# SCH_DFM_PCB_2023-04-27.net
KiCad netlist of a schematic drawn in EasyEDA
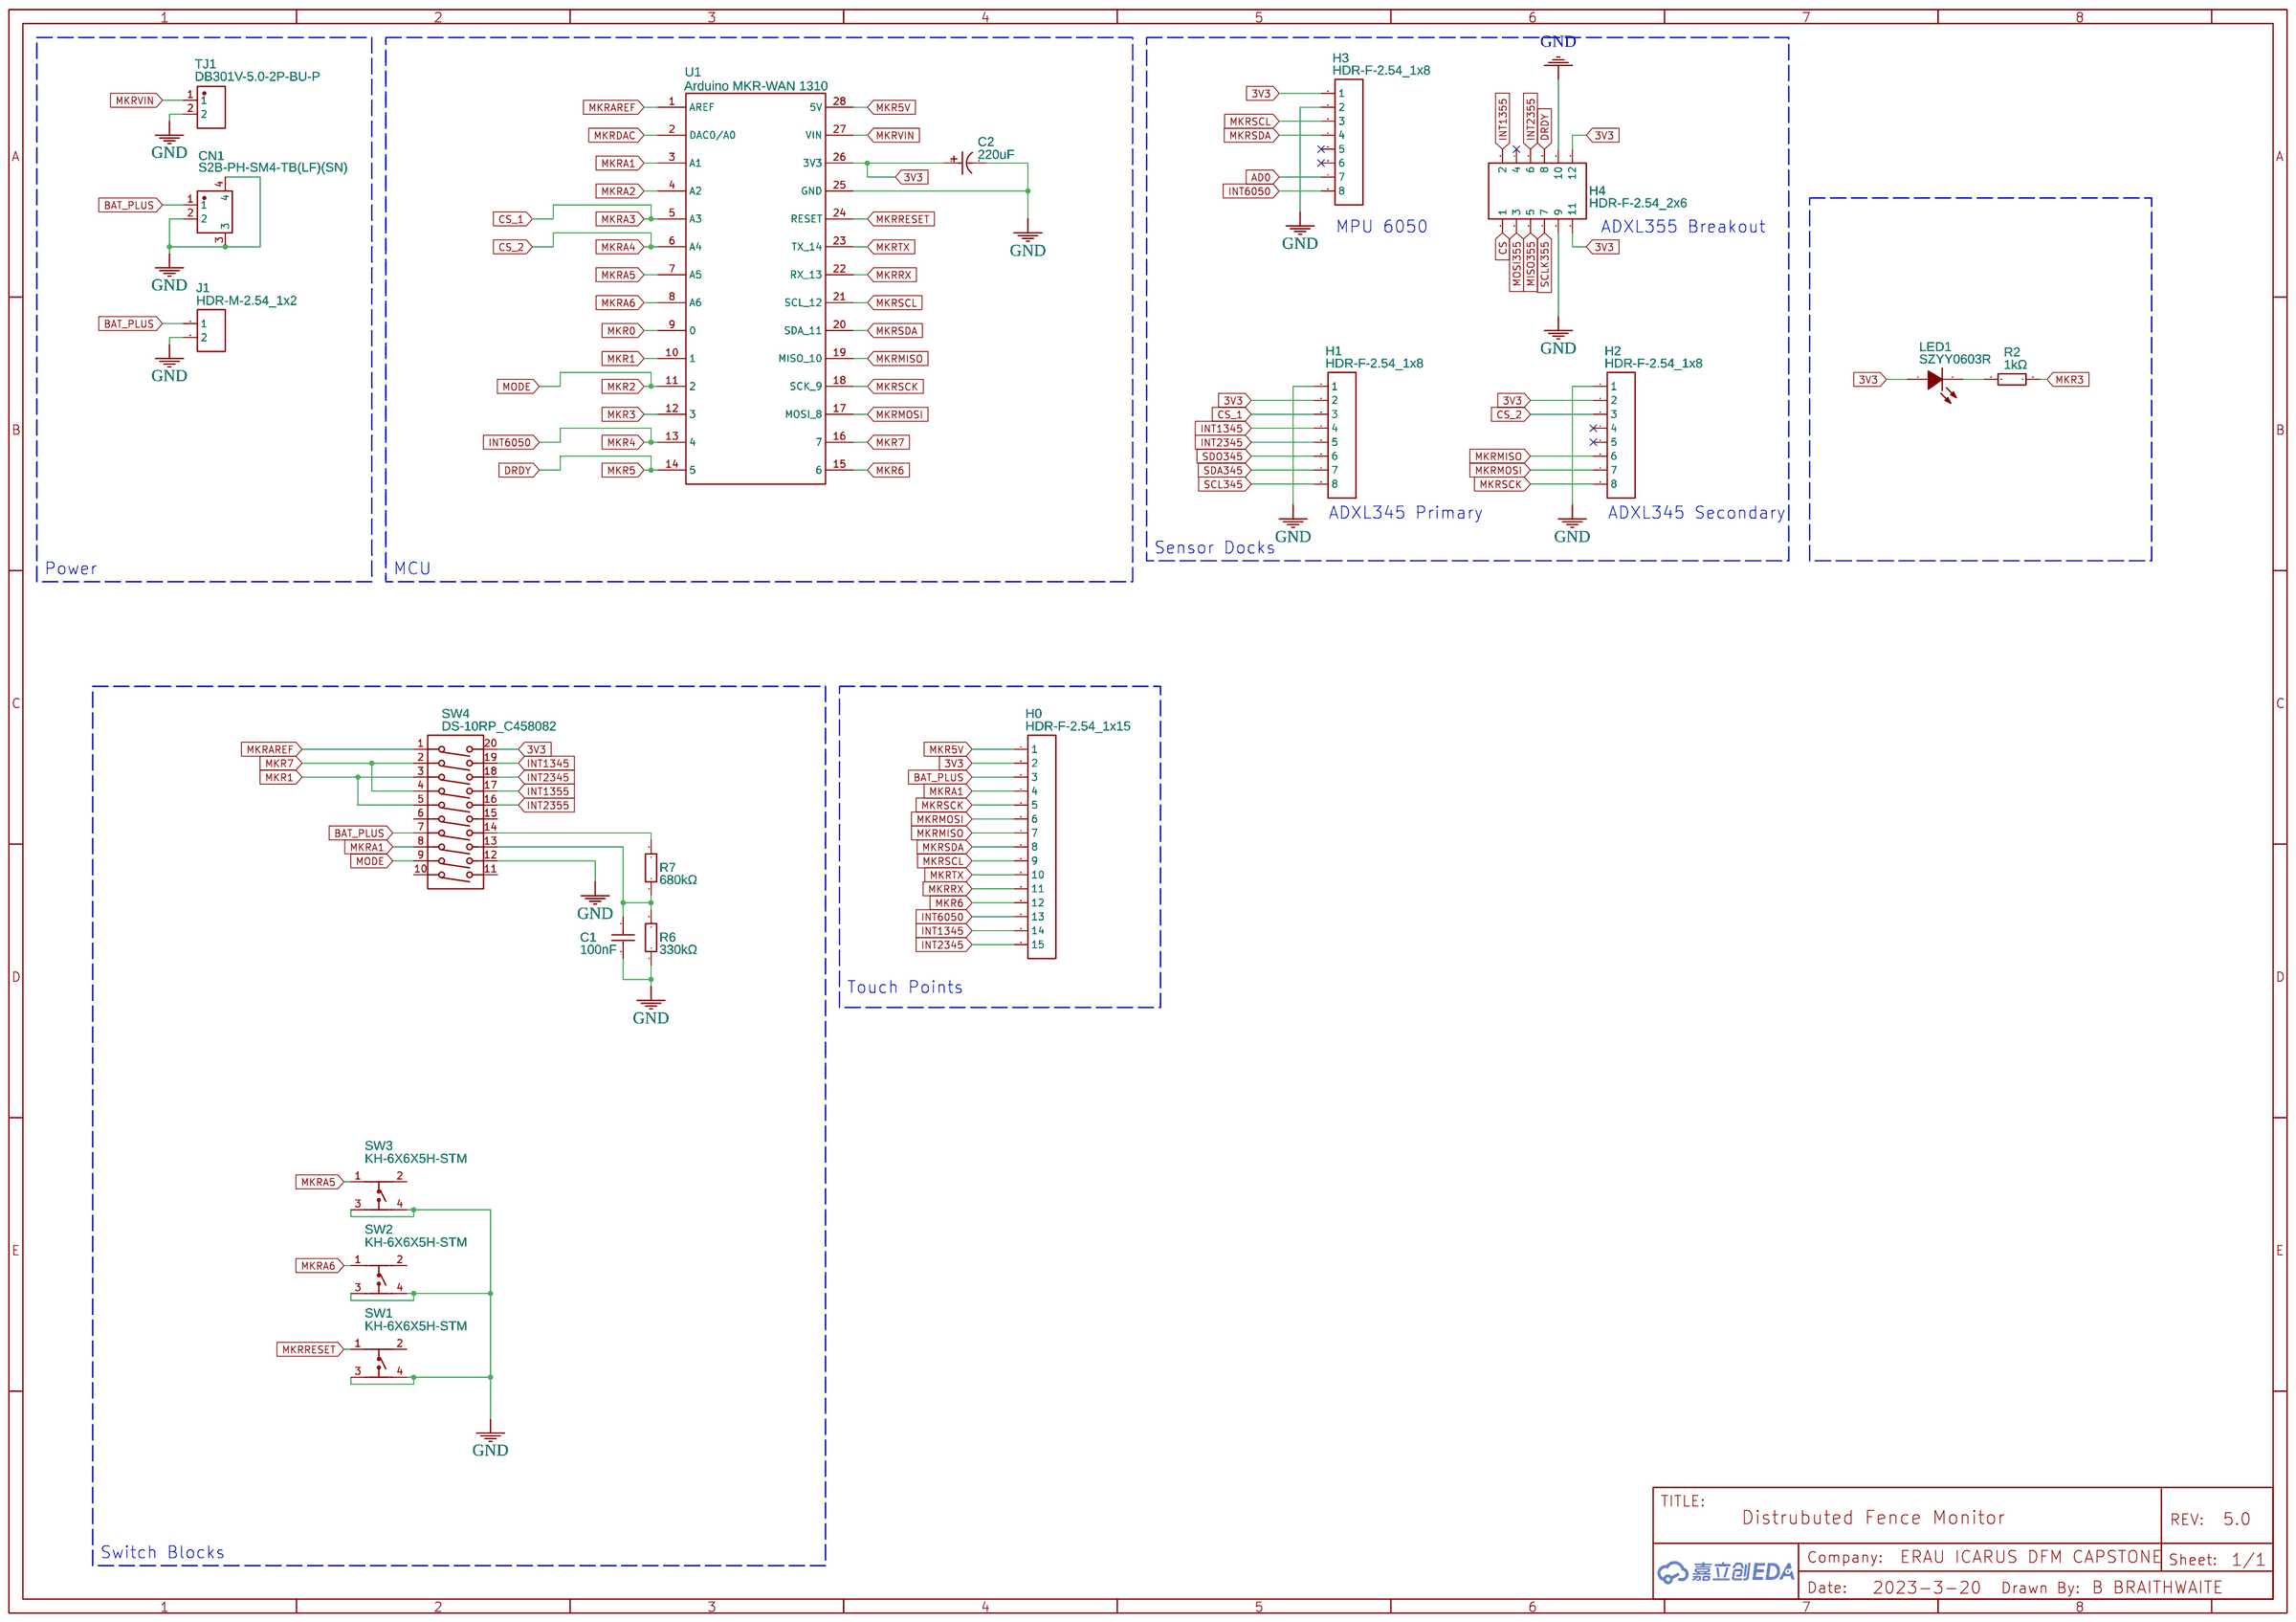
[diagram p0: schematic sheet]

(export (version "E")
  (design (tool "Eeschema 10.0.6"))
  (components
    (comp (ref "C1")
      (value "100nF")
      (fields
        (field (name "BOM_Manufacturer Part") "0603B104K500NT")
        (field (name "BOM_Supplier Part") "C30926")
      )
      (libsource (lib "") (part "0603B104K500NT"))
    )
    (comp (ref "C2")
      (value "220uF")
      (fields
        (field (name "BOM_Manufacturer Part") "RVT1A221M0605")
        (field (name "BOM_Supplier Part") "C72494")
      )
      (libsource (lib "") (part "RVT1A221M0605-C72494"))
    )
    (comp (ref "CN1")
      (value "S2B-PH-SM4-TB(LF)(SN)")
      (fields (field (name "BOM_Supplier Part") "C295747"))
      (libsource (lib "") (part "S2B-PH-SM4-TB(LF)(SN)"))
    )
    (comp (ref "H0")
      (value "HDR-F-2.54_1x15")
      (fields (field (name "BOM_Supplier Part") "C124408"))
      (libsource (lib "") (part "HDR-F-2.54_1x15"))
    )
    (comp (ref "H1")
      (value "HDR-F-2.54_1x8")
      (fields (field (name "BOM_Supplier Part") "C225505"))
      (libsource (lib "") (part "HDR-F-2.54_1x8"))
    )
    (comp (ref "H2")
      (value "HDR-F-2.54_1x8")
      (fields (field (name "BOM_Supplier Part") "C225505"))
      (libsource (lib "") (part "HDR-F-2.54_1x8"))
    )
    (comp (ref "H3")
      (value "HDR-F-2.54_1x8")
      (fields (field (name "BOM_Supplier Part") "C225505"))
      (libsource (lib "") (part "HDR-F-2.54_1x8"))
    )
    (comp (ref "H4")
      (value "HDR-F-2.54_2x6")
      (fields (field (name "BOM_Supplier Part") "C36191"))
      (libsource (lib "") (part "HDR-F-2.54_2x6"))
    )
    (comp (ref "J1")
      (value "HDR-M-2.54_1x2")
      (fields (field (name "BOM_Supplier Part") "C124375"))
      (libsource (lib "") (part "HDR-M-2.54_1x2"))
    )
    (comp (ref "LED1")
      (value "SZYY0603R")
      (fields (field (name "BOM_Supplier Part") "C434419"))
      (libsource (lib "") (part "SZYY0603R"))
    )
    (comp (ref "R2")
      (value "1kΩ")
      (fields
        (field (name "BOM_Manufacturer Part") "0805W8F1001T5E")
        (field (name "BOM_Supplier Part") "C17513")
      )
      (libsource (lib "") (part "0805W8F1001T5E"))
    )
    (comp (ref "R6")
      (value "330kΩ")
      (fields
        (field (name "BOM_Manufacturer Part") "0805W8F3303T5E")
        (field (name "BOM_Supplier Part") "C17629")
      )
      (libsource (lib "") (part "0805W8F3303T5E"))
    )
    (comp (ref "R7")
      (value "680kΩ")
      (fields
        (field (name "BOM_Manufacturer Part") "0805W8F6803T5E")
        (field (name "BOM_Supplier Part") "C17797")
      )
      (libsource (lib "") (part "0805W8F6803T5E"))
    )
    (comp (ref "SW1")
      (value "KH-6X6X5H-STM")
      (fields (field (name "BOM_Supplier Part") "C2837531"))
      (libsource (lib "") (part "KH-6X6X5H-STM"))
    )
    (comp (ref "SW2")
      (value "KH-6X6X5H-STM")
      (fields (field (name "BOM_Supplier Part") "C2837531"))
      (libsource (lib "") (part "KH-6X6X5H-STM"))
    )
    (comp (ref "SW3")
      (value "KH-6X6X5H-STM")
      (fields (field (name "BOM_Supplier Part") "C2837531"))
      (libsource (lib "") (part "KH-6X6X5H-STM"))
    )
    (comp (ref "SW4")
      (value "DS-10RP_C458082")
      (fields (field (name "BOM_Manufacturer Part") "DS-10RP") (field (name "BOM_Supplier Part") "C458082"))
      (libsource (lib "") (part "DS-10RP_C458082"))
    )
    (comp (ref "TJ1")
      (value "DB301V-5.0-2P-BU-P")
      (fields (field (name "BOM_Supplier Part") "C430621"))
      (libsource (lib "") (part "DB301V-5.0-2P-BU-P"))
    )
    (comp (ref "U1")
      (value "Arduino MKR-WAN 1310")
      (fields (field (name "BOM_Manufacturer Part") "Arduino MKR GSM 1400"))
      (libsource (lib "") (part "Arduino MKR-WAN 1310"))
    )
  )
  (nets
    (net (code "1") (name "3V3") (class "Default")
      (node (ref "C2") (pin "1") (pinfunction "1_1") (pintype "input"))
      (node (ref "H0") (pin "2") (pinfunction "2_2") (pintype "unspecified"))
      (node (ref "H1") (pin "2") (pinfunction "2_2") (pintype "unspecified"))
      (node (ref "H2") (pin "2") (pinfunction "2_2") (pintype "unspecified"))
      (node (ref "H3") (pin "1") (pinfunction "1_1") (pintype "unspecified"))
      (node (ref "H4") (pin "11") (pinfunction "11_11") (pintype "input"))
      (node (ref "H4") (pin "12") (pinfunction "12_12") (pintype "input"))
      (node (ref "LED1") (pin "1") (pinfunction "+_1") (pintype "unspecified"))
      (node (ref "SW4") (pin "20") (pinfunction "20_20") (pintype "unspecified"))
      (node (ref "U1") (pin "26") (pinfunction "3V3_26") (pintype "unspecified"))
    )
    (net (code "2") (name "AD0") (class "Default")
      (node (ref "H3") (pin "7") (pinfunction "7_7") (pintype "unspecified"))
    )
    (net (code "3") (name "BAT_PLUS") (class "Default")
      (node (ref "CN1") (pin "1") (pinfunction "1_1") (pintype "unspecified"))
      (node (ref "H0") (pin "3") (pinfunction "3_3") (pintype "unspecified"))
      (node (ref "J1") (pin "1") (pinfunction "1_1") (pintype "unspecified"))
      (node (ref "SW4") (pin "7") (pinfunction "7_7") (pintype "unspecified"))
    )
    (net (code "4") (name "CS") (class "Default")
      (node (ref "H4") (pin "1") (pinfunction "1_1") (pintype "input"))
    )
    (net (code "5") (name "CS_1") (class "Default")
      (node (ref "H1") (pin "3") (pinfunction "3_3") (pintype "unspecified"))
      (node (ref "U1") (pin "5") (pinfunction "A3_5") (pintype "unspecified"))
    )
    (net (code "6") (name "CS_2") (class "Default")
      (node (ref "H2") (pin "3") (pinfunction "3_3") (pintype "unspecified"))
      (node (ref "U1") (pin "6") (pinfunction "A4_6") (pintype "unspecified"))
    )
    (net (code "7") (name "DRDY") (class "Default")
      (node (ref "H4") (pin "8") (pinfunction "8_8") (pintype "input"))
      (node (ref "U1") (pin "14") (pinfunction "5_14") (pintype "unspecified"))
    )
    (net (code "8") (name "GND") (class "Default")
      (node (ref "C1") (pin "1") (pinfunction "1_1") (pintype "input"))
      (node (ref "C2") (pin "2") (pinfunction "2_2") (pintype "input"))
      (node (ref "CN1") (pin "2") (pinfunction "2_2") (pintype "unspecified"))
      (node (ref "CN1") (pin "3") (pinfunction "3_3") (pintype "unspecified"))
      (node (ref "CN1") (pin "4") (pinfunction "4_4") (pintype "unspecified"))
      (node (ref "H1") (pin "1") (pinfunction "1_1") (pintype "unspecified"))
      (node (ref "H2") (pin "1") (pinfunction "1_1") (pintype "unspecified"))
      (node (ref "H3") (pin "2") (pinfunction "2_2") (pintype "unspecified"))
      (node (ref "H4") (pin "10") (pinfunction "10_10") (pintype "input"))
      (node (ref "H4") (pin "9") (pinfunction "9_9") (pintype "input"))
      (node (ref "J1") (pin "2") (pinfunction "2_2") (pintype "unspecified"))
      (node (ref "R6") (pin "1") (pinfunction "1_1") (pintype "input"))
      (node (ref "SW1") (pin "3") (pinfunction "3_3") (pintype "unspecified"))
      (node (ref "SW1") (pin "4") (pinfunction "4_4") (pintype "unspecified"))
      (node (ref "SW2") (pin "3") (pinfunction "3_3") (pintype "unspecified"))
      (node (ref "SW2") (pin "4") (pinfunction "4_4") (pintype "unspecified"))
      (node (ref "SW3") (pin "3") (pinfunction "3_3") (pintype "unspecified"))
      (node (ref "SW3") (pin "4") (pinfunction "4_4") (pintype "unspecified"))
      (node (ref "SW4") (pin "12") (pinfunction "12_12") (pintype "unspecified"))
      (node (ref "TJ1") (pin "2") (pinfunction "2_2") (pintype "unspecified"))
      (node (ref "U1") (pin "25") (pinfunction "GND_25") (pintype "unspecified"))
    )
    (net (code "9") (name "INT1345") (class "Default")
      (node (ref "H0") (pin "14") (pinfunction "14_14") (pintype "unspecified"))
      (node (ref "H1") (pin "4") (pinfunction "4_4") (pintype "unspecified"))
      (node (ref "SW4") (pin "19") (pinfunction "19_19") (pintype "unspecified"))
    )
    (net (code "10") (name "INT1355") (class "Default")
      (node (ref "H4") (pin "2") (pinfunction "2_2") (pintype "input"))
      (node (ref "SW4") (pin "17") (pinfunction "17_17") (pintype "unspecified"))
    )
    (net (code "11") (name "INT2345") (class "Default")
      (node (ref "H0") (pin "15") (pinfunction "15_15") (pintype "unspecified"))
      (node (ref "H1") (pin "5") (pinfunction "5_5") (pintype "unspecified"))
      (node (ref "SW4") (pin "18") (pinfunction "18_18") (pintype "unspecified"))
    )
    (net (code "12") (name "INT2355") (class "Default")
      (node (ref "H4") (pin "6") (pinfunction "6_6") (pintype "input"))
      (node (ref "SW4") (pin "16") (pinfunction "16_16") (pintype "unspecified"))
    )
    (net (code "13") (name "INT6050") (class "Default")
      (node (ref "H0") (pin "13") (pinfunction "13_13") (pintype "unspecified"))
      (node (ref "H3") (pin "8") (pinfunction "8_8") (pintype "unspecified"))
      (node (ref "U1") (pin "13") (pinfunction "4_13") (pintype "unspecified"))
    )
    (net (code "14") (name "MISO355") (class "Default")
      (node (ref "H4") (pin "5") (pinfunction "5_5") (pintype "input"))
    )
    (net (code "15") (name "MKR0") (class "Default")
      (node (ref "U1") (pin "9") (pinfunction "0_9") (pintype "unspecified"))
    )
    (net (code "16") (name "MKR1") (class "Default")
      (node (ref "SW4") (pin "3") (pinfunction "3_3") (pintype "unspecified"))
      (node (ref "SW4") (pin "5") (pinfunction "5_5") (pintype "unspecified"))
      (node (ref "U1") (pin "10") (pinfunction "1_10") (pintype "unspecified"))
    )
    (net (code "17") (name "MKR2") (class "Default")
      (node (ref "SW4") (pin "9") (pinfunction "9_9") (pintype "unspecified"))
      (node (ref "U1") (pin "11") (pinfunction "2_11") (pintype "unspecified"))
    )
    (net (code "18") (name "MKR3") (class "Default")
      (node (ref "R2") (pin "2") (pinfunction "2_2") (pintype "input"))
      (node (ref "U1") (pin "12") (pinfunction "3_12") (pintype "unspecified"))
    )
    (net (code "19") (name "MKR5V") (class "Default")
      (node (ref "H0") (pin "1") (pinfunction "1_1") (pintype "unspecified"))
      (node (ref "U1") (pin "28") (pinfunction "5V_28") (pintype "unspecified"))
    )
    (net (code "20") (name "MKR6") (class "Default")
      (node (ref "H0") (pin "12") (pinfunction "12_12") (pintype "unspecified"))
      (node (ref "U1") (pin "15") (pinfunction "6_15") (pintype "unspecified"))
    )
    (net (code "21") (name "MKR7") (class "Default")
      (node (ref "SW4") (pin "2") (pinfunction "2_2") (pintype "unspecified"))
      (node (ref "SW4") (pin "4") (pinfunction "4_4") (pintype "unspecified"))
      (node (ref "U1") (pin "16") (pinfunction "7_16") (pintype "unspecified"))
    )
    (net (code "22") (name "MKRA1") (class "Default")
      (node (ref "H0") (pin "4") (pinfunction "4_4") (pintype "unspecified"))
      (node (ref "SW4") (pin "8") (pinfunction "8_8") (pintype "unspecified"))
      (node (ref "U1") (pin "3") (pinfunction "A1_3") (pintype "unspecified"))
    )
    (net (code "23") (name "MKRA2") (class "Default")
      (node (ref "U1") (pin "4") (pinfunction "A2_4") (pintype "unspecified"))
    )
    (net (code "24") (name "MKRA5") (class "Default")
      (node (ref "SW3") (pin "1") (pinfunction "1_1") (pintype "unspecified"))
      (node (ref "U1") (pin "7") (pinfunction "A5_7") (pintype "unspecified"))
    )
    (net (code "25") (name "MKRA6") (class "Default")
      (node (ref "SW2") (pin "1") (pinfunction "1_1") (pintype "unspecified"))
      (node (ref "U1") (pin "8") (pinfunction "A6_8") (pintype "unspecified"))
    )
    (net (code "26") (name "MKRAREF") (class "Default")
      (node (ref "SW4") (pin "1") (pinfunction "1_1") (pintype "unspecified"))
      (node (ref "U1") (pin "1") (pinfunction "AREF_1") (pintype "unspecified"))
    )
    (net (code "27") (name "MKRDAC") (class "Default")
      (node (ref "U1") (pin "2") (pinfunction "DAC0/A0_2") (pintype "unspecified"))
    )
    (net (code "28") (name "MKRMISO") (class "Default")
      (node (ref "H0") (pin "7") (pinfunction "7_7") (pintype "unspecified"))
      (node (ref "H2") (pin "6") (pinfunction "6_6") (pintype "unspecified"))
      (node (ref "U1") (pin "19") (pinfunction "MISO_10_19") (pintype "unspecified"))
    )
    (net (code "29") (name "MKRMOSI") (class "Default")
      (node (ref "H0") (pin "6") (pinfunction "6_6") (pintype "unspecified"))
      (node (ref "H2") (pin "7") (pinfunction "7_7") (pintype "unspecified"))
      (node (ref "U1") (pin "17") (pinfunction "MOSI_8_17") (pintype "unspecified"))
    )
    (net (code "30") (name "MKRRESET") (class "Default")
      (node (ref "SW1") (pin "1") (pinfunction "1_1") (pintype "unspecified"))
      (node (ref "U1") (pin "24") (pinfunction "RESET_24") (pintype "unspecified"))
    )
    (net (code "31") (name "MKRRX") (class "Default")
      (node (ref "H0") (pin "11") (pinfunction "11_11") (pintype "unspecified"))
      (node (ref "U1") (pin "22") (pinfunction "RX_13_22") (pintype "unspecified"))
    )
    (net (code "32") (name "MKRSCK") (class "Default")
      (node (ref "H0") (pin "5") (pinfunction "5_5") (pintype "unspecified"))
      (node (ref "H2") (pin "8") (pinfunction "8_8") (pintype "unspecified"))
      (node (ref "U1") (pin "18") (pinfunction "SCK_9_18") (pintype "unspecified"))
    )
    (net (code "33") (name "MKRSCL") (class "Default")
      (node (ref "H0") (pin "9") (pinfunction "9_9") (pintype "unspecified"))
      (node (ref "H3") (pin "3") (pinfunction "3_3") (pintype "unspecified"))
      (node (ref "U1") (pin "21") (pinfunction "SCL_12_21") (pintype "unspecified"))
    )
    (net (code "34") (name "MKRSDA") (class "Default")
      (node (ref "H0") (pin "8") (pinfunction "8_8") (pintype "unspecified"))
      (node (ref "H3") (pin "4") (pinfunction "4_4") (pintype "unspecified"))
      (node (ref "U1") (pin "20") (pinfunction "SDA_11_20") (pintype "unspecified"))
    )
    (net (code "35") (name "MKRTX") (class "Default")
      (node (ref "H0") (pin "10") (pinfunction "10_10") (pintype "unspecified"))
      (node (ref "U1") (pin "23") (pinfunction "TX_14_23") (pintype "unspecified"))
    )
    (net (code "36") (name "MKRVIN") (class "Default")
      (node (ref "TJ1") (pin "1") (pinfunction "1_1") (pintype "unspecified"))
      (node (ref "U1") (pin "27") (pinfunction "VIN_27") (pintype "unspecified"))
    )
    (net (code "37") (name "MOSI355") (class "Default")
      (node (ref "H4") (pin "3") (pinfunction "3_3") (pintype "input"))
    )
    (net (code "38") (name "Net-(C1-Pad2)") (class "Default")
      (node (ref "C1") (pin "2") (pinfunction "2_2") (pintype "input"))
      (node (ref "R6") (pin "2") (pinfunction "2_2") (pintype "input"))
      (node (ref "R7") (pin "1") (pinfunction "1_1") (pintype "input"))
      (node (ref "SW4") (pin "13") (pinfunction "13_13") (pintype "unspecified"))
    )
    (net (code "39") (name "Net-(LED1--)") (class "Default")
      (node (ref "LED1") (pin "2") (pinfunction "-_2") (pintype "unspecified"))
      (node (ref "R2") (pin "1") (pinfunction "1_1") (pintype "input"))
    )
    (net (code "40") (name "Net-(R7-Pad2)") (class "Default")
      (node (ref "R7") (pin "2") (pinfunction "2_2") (pintype "input"))
      (node (ref "SW4") (pin "14") (pinfunction "14_14") (pintype "unspecified"))
    )
    (net (code "41") (name "SCL345") (class "Default")
      (node (ref "H1") (pin "8") (pinfunction "8_8") (pintype "unspecified"))
    )
    (net (code "42") (name "SCLK355") (class "Default")
      (node (ref "H4") (pin "7") (pinfunction "7_7") (pintype "input"))
    )
    (net (code "43") (name "SDA345") (class "Default")
      (node (ref "H1") (pin "7") (pinfunction "7_7") (pintype "unspecified"))
    )
    (net (code "44") (name "SDO345") (class "Default")
      (node (ref "H1") (pin "6") (pinfunction "6_6") (pintype "unspecified"))
    )
    (net (code "45") (name "unconnected-(H2-Pad4)") (class "Default")
      (node (ref "H2") (pin "4") (pinfunction "4_4") (pintype "unspecified+no_connect"))
    )
    (net (code "46") (name "unconnected-(H2-Pad5)") (class "Default")
      (node (ref "H2") (pin "5") (pinfunction "5_5") (pintype "unspecified+no_connect"))
    )
    (net (code "47") (name "unconnected-(H3-Pad5)") (class "Default")
      (node (ref "H3") (pin "5") (pinfunction "5_5") (pintype "unspecified+no_connect"))
    )
    (net (code "48") (name "unconnected-(H3-Pad6)") (class "Default")
      (node (ref "H3") (pin "6") (pinfunction "6_6") (pintype "unspecified+no_connect"))
    )
    (net (code "49") (name "unconnected-(H4-Pad4)") (class "Default")
      (node (ref "H4") (pin "4") (pinfunction "4_4") (pintype "input+no_connect"))
    )
    (net (code "50") (name "unconnected-(SW1-Pad2)") (class "Default")
      (node (ref "SW1") (pin "2") (pinfunction "2_2") (pintype "unspecified"))
    )
    (net (code "51") (name "unconnected-(SW2-Pad2)") (class "Default")
      (node (ref "SW2") (pin "2") (pinfunction "2_2") (pintype "unspecified"))
    )
    (net (code "52") (name "unconnected-(SW3-Pad2)") (class "Default")
      (node (ref "SW3") (pin "2") (pinfunction "2_2") (pintype "unspecified"))
    )
    (net (code "53") (name "unconnected-(SW4-Pad6)") (class "Default")
      (node (ref "SW4") (pin "6") (pinfunction "6_6") (pintype "unspecified"))
    )
    (net (code "54") (name "unconnected-(SW4-Pad10)") (class "Default")
      (node (ref "SW4") (pin "10") (pinfunction "10_10") (pintype "unspecified"))
    )
    (net (code "55") (name "unconnected-(SW4-Pad11)") (class "Default")
      (node (ref "SW4") (pin "11") (pinfunction "11_11") (pintype "unspecified"))
    )
    (net (code "56") (name "unconnected-(SW4-Pad15)") (class "Default")
      (node (ref "SW4") (pin "15") (pinfunction "15_15") (pintype "unspecified"))
    )
  )
)
